# BASE.net
KiCad netlist of a schematic drawn in Altium Designer
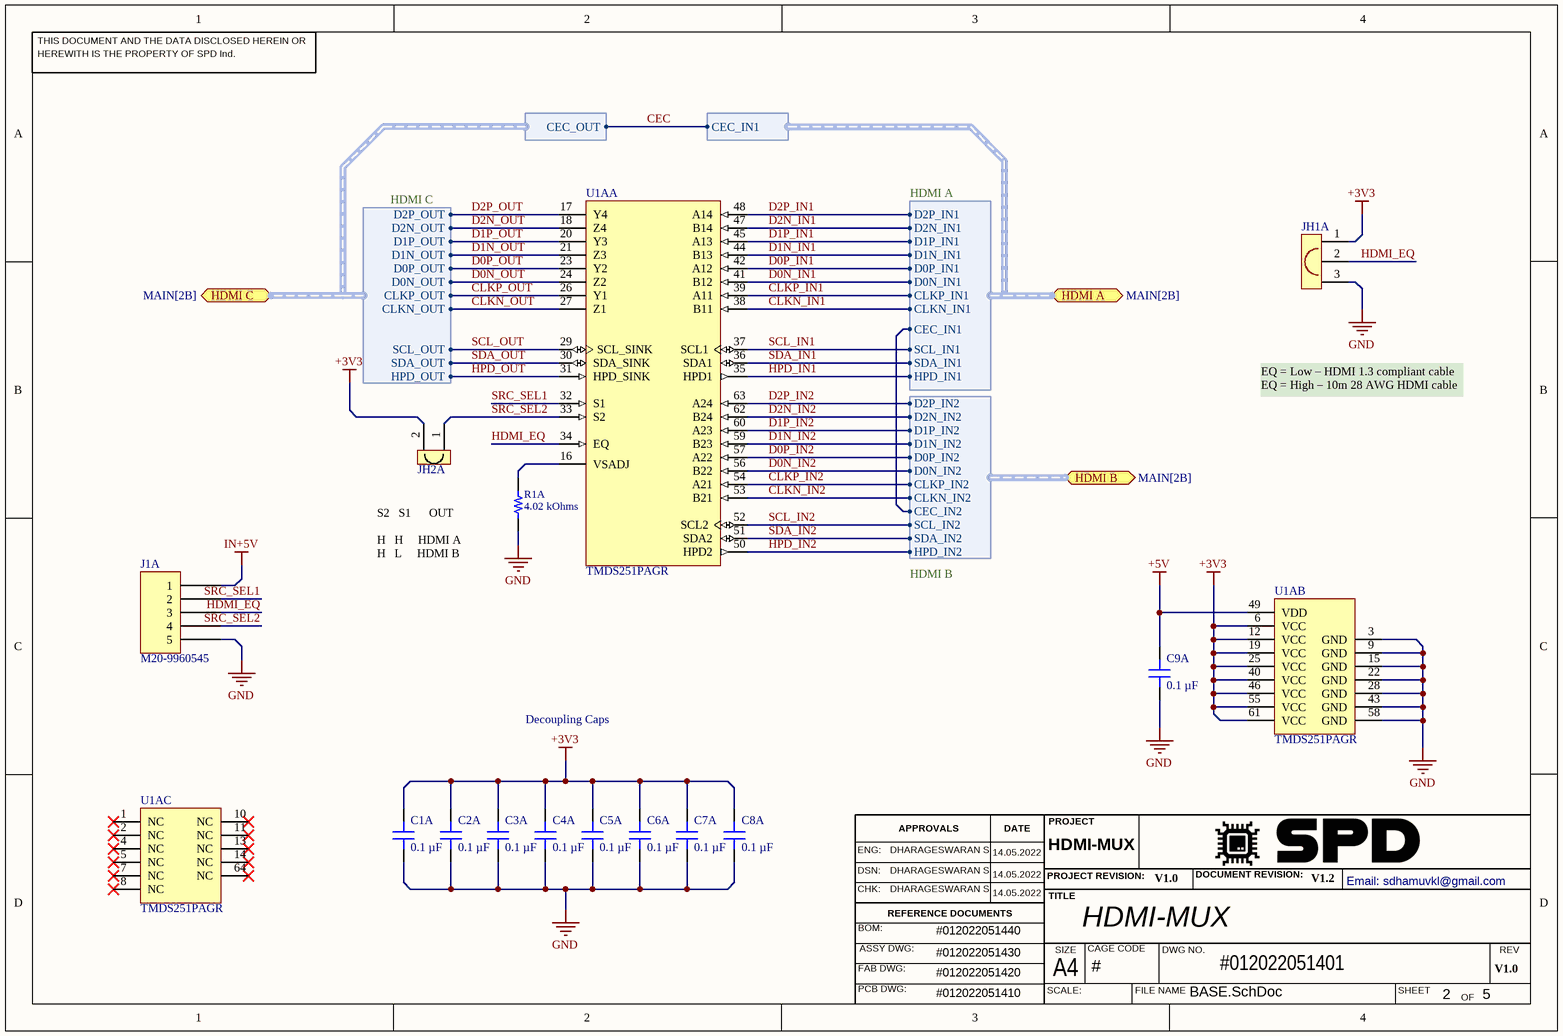
[diagram p0: BASE.SchDoc]

(export (version "E")
  (design (tool "Eeschema 10.0.6"))
  (components
    (comp (ref "C1A")
      (value "0.1 µF")
      (footprint "CAP 0402_1005")
      (description "CAP CER 100NF 10V X7R 0402")
      (fields
        (field (name "PART NUMBER") "CL05B104KP5VPNC")
        (field (name "MANUFACTURER") "Samsung Electro-Mechanics")
      )
      (libsource (lib "Postgres Altium Library - altium_library") (part "Capacitor"))
    )
    (comp (ref "C2A")
      (value "0.1 µF")
      (footprint "CAP 0402_1005")
      (description "CAP CER 100NF 10V X7R 0402")
      (fields
        (field (name "PART NUMBER") "CL05B104KP5VPNC")
        (field (name "MANUFACTURER") "Samsung Electro-Mechanics")
      )
      (libsource (lib "Postgres Altium Library - altium_library") (part "Capacitor"))
    )
    (comp (ref "C3A")
      (value "0.1 µF")
      (footprint "CAP 0402_1005")
      (description "CAP CER 100NF 10V X7R 0402")
      (fields
        (field (name "PART NUMBER") "CL05B104KP5VPNC")
        (field (name "MANUFACTURER") "Samsung Electro-Mechanics")
      )
      (libsource (lib "Postgres Altium Library - altium_library") (part "Capacitor"))
    )
    (comp (ref "C4A")
      (value "0.1 µF")
      (footprint "CAP 0402_1005")
      (description "CAP CER 100NF 10V X7R 0402")
      (fields
        (field (name "PART NUMBER") "CL05B104KP5VPNC")
        (field (name "MANUFACTURER") "Samsung Electro-Mechanics")
      )
      (libsource (lib "Postgres Altium Library - altium_library") (part "Capacitor"))
    )
    (comp (ref "C5A")
      (value "0.1 µF")
      (footprint "CAP 0402_1005")
      (description "CAP CER 100NF 10V X7R 0402")
      (fields
        (field (name "PART NUMBER") "CL05B104KP5VPNC")
        (field (name "MANUFACTURER") "Samsung Electro-Mechanics")
      )
      (libsource (lib "Postgres Altium Library - altium_library") (part "Capacitor"))
    )
    (comp (ref "C6A")
      (value "0.1 µF")
      (footprint "CAP 0402_1005")
      (description "CAP CER 100NF 10V X7R 0402")
      (fields
        (field (name "PART NUMBER") "CL05B104KP5VPNC")
        (field (name "MANUFACTURER") "Samsung Electro-Mechanics")
      )
      (libsource (lib "Postgres Altium Library - altium_library") (part "Capacitor"))
    )
    (comp (ref "C7A")
      (value "0.1 µF")
      (footprint "CAP 0402_1005")
      (description "CAP CER 100NF 10V X7R 0402")
      (fields
        (field (name "PART NUMBER") "CL05B104KP5VPNC")
        (field (name "MANUFACTURER") "Samsung Electro-Mechanics")
      )
      (libsource (lib "Postgres Altium Library - altium_library") (part "Capacitor"))
    )
    (comp (ref "C8A")
      (value "0.1 µF")
      (footprint "CAP 0402_1005")
      (description "CAP CER 100NF 10V X7R 0402")
      (fields
        (field (name "PART NUMBER") "CL05B104KP5VPNC")
        (field (name "MANUFACTURER") "Samsung Electro-Mechanics")
      )
      (libsource (lib "Postgres Altium Library - altium_library") (part "Capacitor"))
    )
    (comp (ref "C9A")
      (value "0.1 µF")
      (footprint "CAP 0402_1005")
      (description "CAP CER 100NF 10V X7R 0402")
      (fields
        (field (name "PART NUMBER") "CL05B104KP5VPNC")
        (field (name "MANUFACTURER") "Samsung Electro-Mechanics")
      )
      (libsource (lib "Postgres Altium Library - altium_library") (part "Capacitor"))
    )
    (comp (ref "J1A")
      (value "M20-9960545")
      (footprint "HARWIN M20-9960545")
      (description "CONN HEADER R/A 5POS 2.54MM")
      (fields (field (name "MANUFACTURER") "Harwin Inc."))
      (libsource (lib "Postgres Altium Library - altium_library") (part "5 Pin"))
    )
    (comp (ref "JH1A")
      (value "3PIN-JUMPER-RED")
      (footprint "JUMPER-3PIN-RED")
      (libsource (lib "Jumper-TH") (part "3PIN-JUMPER-RED"))
    )
    (comp (ref "JH2A")
      (value "2PIN-JUMPER-BLACK")
      (footprint "JUMPER-2PIN-BLACK")
      (libsource (lib "Jumper-TH") (part "2PIN-JUMPER-BLACK"))
    )
    (comp (ref "R1A")
      (value "4.02 kOhms")
      (footprint "RES 0402_1005")
      (description "RES SMD 4.02K OHM 1% 1/16W 0402")
      (fields (field (name "PART NUMBER") "CR0402-FX-4021GLF") (field (name "TOLERANCE") "±1%"))
      (libsource (lib "Postgres Altium Library - altium_library") (part "Resistor"))
    )
    (comp (ref "U1A")
      (value "TMDS251PAGR")
      (footprint "PAG0064A_L")
      (fields (field (name "MANUFACTURER") "Texas Instruments"))
      (libsource (lib "TMDS251") (part "CMP-0325-00084-3"))
    )
  )
  (nets
    (net (code "5") (name "+3V3") (class "Default")
      (node (ref "C1A") (pin "2") (pinfunction "2_2") (pintype "passive"))
      (node (ref "C2A") (pin "2") (pinfunction "2_2") (pintype "passive"))
      (node (ref "C3A") (pin "2") (pinfunction "2_2") (pintype "passive"))
      (node (ref "C4A") (pin "2") (pinfunction "2_2") (pintype "passive"))
      (node (ref "C5A") (pin "2") (pinfunction "2_2") (pintype "passive"))
      (node (ref "C6A") (pin "2") (pinfunction "2_2") (pintype "passive"))
      (node (ref "C7A") (pin "2") (pinfunction "2_2") (pintype "passive"))
      (node (ref "C8A") (pin "2") (pinfunction "2_2") (pintype "passive"))
      (node (ref "JH1A") (pin "1") (pinfunction "1_1") (pintype "passive"))
      (node (ref "JH2A") (pin "2") (pintype "passive"))
      (node (ref "U1A") (pin "12") (pinfunction "VCC_12") (pintype "power_in"))
      (node (ref "U1A") (pin "19") (pinfunction "VCC_19") (pintype "power_in"))
      (node (ref "U1A") (pin "25") (pinfunction "VCC_25") (pintype "power_in"))
      (node (ref "U1A") (pin "40") (pinfunction "VCC_40") (pintype "power_in"))
      (node (ref "U1A") (pin "46") (pinfunction "VCC_46") (pintype "power_in"))
      (node (ref "U1A") (pin "55") (pinfunction "VCC_55") (pintype "power_in"))
      (node (ref "U1A") (pin "6") (pinfunction "VCC_6") (pintype "power_in"))
      (node (ref "U1A") (pin "61") (pinfunction "VCC_61") (pintype "power_in"))
    )
    (net (code "6") (name "+5V") (class "Default")
      (node (ref "C9A") (pin "2") (pinfunction "2_2") (pintype "passive"))
      (node (ref "U1A") (pin "49") (pinfunction "VDD_49") (pintype "power_in"))
    )
    (net (code "8") (name "/CLKN_IN1") (class "Default")
      (node (ref "U1A") (pin "38") (pinfunction "B11_38") (pintype "input"))
    )
    (net (code "9") (name "/CLKN_IN2") (class "Default")
      (node (ref "U1A") (pin "53") (pinfunction "B21_53") (pintype "input"))
    )
    (net (code "10") (name "/CLKN_OUT") (class "Default")
      (node (ref "U1A") (pin "27") (pinfunction "Z1_27") (pintype "tri_state"))
    )
    (net (code "11") (name "/CLKP_IN1") (class "Default")
      (node (ref "U1A") (pin "39") (pinfunction "A11_39") (pintype "input"))
    )
    (net (code "12") (name "/CLKP_IN2") (class "Default")
      (node (ref "U1A") (pin "54") (pinfunction "A21_54") (pintype "input"))
    )
    (net (code "13") (name "/CLKP_OUT") (class "Default")
      (node (ref "U1A") (pin "26") (pinfunction "Y1_26") (pintype "tri_state"))
    )
    (net (code "14") (name "/D0N_IN1") (class "Default")
      (node (ref "U1A") (pin "41") (pinfunction "B12_41") (pintype "input"))
    )
    (net (code "15") (name "/D0N_IN2") (class "Default")
      (node (ref "U1A") (pin "56") (pinfunction "B22_56") (pintype "input"))
    )
    (net (code "16") (name "/D0N_OUT") (class "Default")
      (node (ref "U1A") (pin "24") (pinfunction "Z2_24") (pintype "tri_state"))
    )
    (net (code "17") (name "/D0P_IN1") (class "Default")
      (node (ref "U1A") (pin "42") (pinfunction "A12_42") (pintype "input"))
    )
    (net (code "18") (name "/D0P_IN2") (class "Default")
      (node (ref "U1A") (pin "57") (pinfunction "A22_57") (pintype "input"))
    )
    (net (code "19") (name "/D0P_OUT") (class "Default")
      (node (ref "U1A") (pin "23") (pinfunction "Y2_23") (pintype "tri_state"))
    )
    (net (code "20") (name "/D1N_IN1") (class "Default")
      (node (ref "U1A") (pin "44") (pinfunction "B13_44") (pintype "input"))
    )
    (net (code "21") (name "/D1N_IN2") (class "Default")
      (node (ref "U1A") (pin "59") (pinfunction "B23_59") (pintype "input"))
    )
    (net (code "22") (name "/D1N_OUT") (class "Default")
      (node (ref "U1A") (pin "21") (pinfunction "Z3_21") (pintype "tri_state"))
    )
    (net (code "23") (name "/D1P_IN1") (class "Default")
      (node (ref "U1A") (pin "45") (pinfunction "A13_45") (pintype "input"))
    )
    (net (code "24") (name "/D1P_IN2") (class "Default")
      (node (ref "U1A") (pin "60") (pinfunction "A23_60") (pintype "input"))
    )
    (net (code "25") (name "/D1P_OUT") (class "Default")
      (node (ref "U1A") (pin "20") (pinfunction "Y3_20") (pintype "tri_state"))
    )
    (net (code "26") (name "/D2N_IN1") (class "Default")
      (node (ref "U1A") (pin "47") (pinfunction "B14_47") (pintype "input"))
    )
    (net (code "27") (name "/D2N_IN2") (class "Default")
      (node (ref "U1A") (pin "62") (pinfunction "B24_62") (pintype "input"))
    )
    (net (code "28") (name "/D2N_OUT") (class "Default")
      (node (ref "U1A") (pin "18") (pinfunction "Z4_18") (pintype "tri_state"))
    )
    (net (code "29") (name "/D2P_IN1") (class "Default")
      (node (ref "U1A") (pin "48") (pinfunction "A14_48") (pintype "input"))
    )
    (net (code "30") (name "/D2P_IN2") (class "Default")
      (node (ref "U1A") (pin "63") (pinfunction "A24_63") (pintype "input"))
    )
    (net (code "31") (name "/D2P_OUT") (class "Default")
      (node (ref "U1A") (pin "17") (pinfunction "Y4_17") (pintype "tri_state"))
    )
    (net (code "32") (name "/HDMI_EQ") (class "Default")
      (node (ref "J1A") (pin "3") (pinfunction "3_3") (pintype "passive"))
      (node (ref "JH1A") (pin "2") (pinfunction "2_2") (pintype "passive"))
      (node (ref "U1A") (pin "34") (pinfunction "EQ_34") (pintype "input"))
    )
    (net (code "33") (name "/HPD_IN1") (class "Default")
      (node (ref "U1A") (pin "35") (pinfunction "HPD1_35") (pintype "output"))
    )
    (net (code "34") (name "/HPD_IN2") (class "Default")
      (node (ref "U1A") (pin "50") (pinfunction "HPD2_50") (pintype "output"))
    )
    (net (code "35") (name "/HPD_OUT") (class "Default")
      (node (ref "U1A") (pin "31") (pinfunction "HPD_SINK_31") (pintype "input"))
    )
    (net (code "36") (name "/SCL_IN1") (class "Default")
      (node (ref "U1A") (pin "37") (pinfunction "SCL1_37") (pintype "bidirectional"))
    )
    (net (code "37") (name "/SCL_IN2") (class "Default")
      (node (ref "U1A") (pin "52") (pinfunction "SCL2_52") (pintype "bidirectional"))
    )
    (net (code "38") (name "/SCL_OUT") (class "Default")
      (node (ref "U1A") (pin "29") (pinfunction "SCL_SINK_29") (pintype "bidirectional"))
    )
    (net (code "39") (name "/SDA_IN1") (class "Default")
      (node (ref "U1A") (pin "36") (pinfunction "SDA1_36") (pintype "bidirectional"))
    )
    (net (code "40") (name "/SDA_IN2") (class "Default")
      (node (ref "U1A") (pin "51") (pinfunction "SDA2_51") (pintype "bidirectional"))
    )
    (net (code "41") (name "/SDA_OUT") (class "Default")
      (node (ref "U1A") (pin "30") (pinfunction "SDA_SINK_30") (pintype "bidirectional"))
    )
    (net (code "42") (name "/SRC_SEL1") (class "Default")
      (node (ref "J1A") (pin "2") (pinfunction "2_2") (pintype "passive"))
      (node (ref "U1A") (pin "32") (pinfunction "S1_32") (pintype "input"))
    )
    (net (code "43") (name "/SRC_SEL2") (class "Default")
      (node (ref "J1A") (pin "4") (pinfunction "4_4") (pintype "passive"))
      (node (ref "JH2A") (pin "1") (pintype "passive"))
      (node (ref "U1A") (pin "33") (pinfunction "S2_33") (pintype "input"))
    )
    (net (code "47") (name "GND") (class "Default")
      (node (ref "C1A") (pin "1") (pinfunction "1_1") (pintype "passive"))
      (node (ref "C2A") (pin "1") (pinfunction "1_1") (pintype "passive"))
      (node (ref "C3A") (pin "1") (pinfunction "1_1") (pintype "passive"))
      (node (ref "C4A") (pin "1") (pinfunction "1_1") (pintype "passive"))
      (node (ref "C5A") (pin "1") (pinfunction "1_1") (pintype "passive"))
      (node (ref "C6A") (pin "1") (pinfunction "1_1") (pintype "passive"))
      (node (ref "C7A") (pin "1") (pinfunction "1_1") (pintype "passive"))
      (node (ref "C8A") (pin "1") (pinfunction "1_1") (pintype "passive"))
      (node (ref "C9A") (pin "1") (pinfunction "1_1") (pintype "passive"))
      (node (ref "J1A") (pin "5") (pinfunction "5_5") (pintype "passive"))
      (node (ref "JH1A") (pin "3") (pinfunction "3_3") (pintype "passive"))
      (node (ref "R1A") (pin "1") (pinfunction "1_1") (pintype "passive"))
      (node (ref "U1A") (pin "15") (pinfunction "GND_15") (pintype "power_in"))
      (node (ref "U1A") (pin "22") (pinfunction "GND_22") (pintype "power_in"))
      (node (ref "U1A") (pin "28") (pinfunction "GND_28") (pintype "power_in"))
      (node (ref "U1A") (pin "3") (pinfunction "GND_3") (pintype "power_in"))
      (node (ref "U1A") (pin "43") (pinfunction "GND_43") (pintype "power_in"))
      (node (ref "U1A") (pin "58") (pinfunction "GND_58") (pintype "power_in"))
      (node (ref "U1A") (pin "9") (pinfunction "GND_9") (pintype "power_in"))
    )
    (net (code "48") (name "IN+5V") (class "Default")
      (node (ref "J1A") (pin "1") (pinfunction "1_1") (pintype "passive"))
    )
    (net (code "49") (name "Net-(U1AA-VSADJ)") (class "Default")
      (node (ref "R1A") (pin "2") (pinfunction "2_2") (pintype "passive"))
      (node (ref "U1A") (pin "16") (pinfunction "VSADJ_16") (pintype "tri_state"))
    )
    (net (code "50") (name "unconnected-(U1AC-NC-Pad1)") (class "Default")
      (node (ref "U1A") (pin "1") (pinfunction "NC_1") (pintype "passive+no_connect"))
    )
    (net (code "51") (name "unconnected-(U1AC-NC-Pad2)") (class "Default")
      (node (ref "U1A") (pin "2") (pinfunction "NC_2") (pintype "passive+no_connect"))
    )
    (net (code "52") (name "unconnected-(U1AC-NC-Pad4)") (class "Default")
      (node (ref "U1A") (pin "4") (pinfunction "NC_4") (pintype "passive+no_connect"))
    )
    (net (code "53") (name "unconnected-(U1AC-NC-Pad5)") (class "Default")
      (node (ref "U1A") (pin "5") (pinfunction "NC_5") (pintype "passive+no_connect"))
    )
    (net (code "54") (name "unconnected-(U1AC-NC-Pad7)") (class "Default")
      (node (ref "U1A") (pin "7") (pinfunction "NC_7") (pintype "passive+no_connect"))
    )
    (net (code "55") (name "unconnected-(U1AC-NC-Pad8)") (class "Default")
      (node (ref "U1A") (pin "8") (pinfunction "NC_8") (pintype "passive+no_connect"))
    )
    (net (code "56") (name "unconnected-(U1AC-NC-Pad10)") (class "Default")
      (node (ref "U1A") (pin "10") (pinfunction "NC_10") (pintype "passive+no_connect"))
    )
    (net (code "57") (name "unconnected-(U1AC-NC-Pad11)") (class "Default")
      (node (ref "U1A") (pin "11") (pinfunction "NC_11") (pintype "passive+no_connect"))
    )
    (net (code "58") (name "unconnected-(U1AC-NC-Pad13)") (class "Default")
      (node (ref "U1A") (pin "13") (pinfunction "NC_13") (pintype "passive+no_connect"))
    )
    (net (code "59") (name "unconnected-(U1AC-NC-Pad14)") (class "Default")
      (node (ref "U1A") (pin "14") (pinfunction "NC_14") (pintype "passive+no_connect"))
    )
    (net (code "60") (name "unconnected-(U1AC-NC-Pad64)") (class "Default")
      (node (ref "U1A") (pin "64") (pinfunction "NC_64") (pintype "passive+no_connect"))
    )
  )
)
